# Quark_One.net
KiCad netlist of a schematic drawn in EAGLE
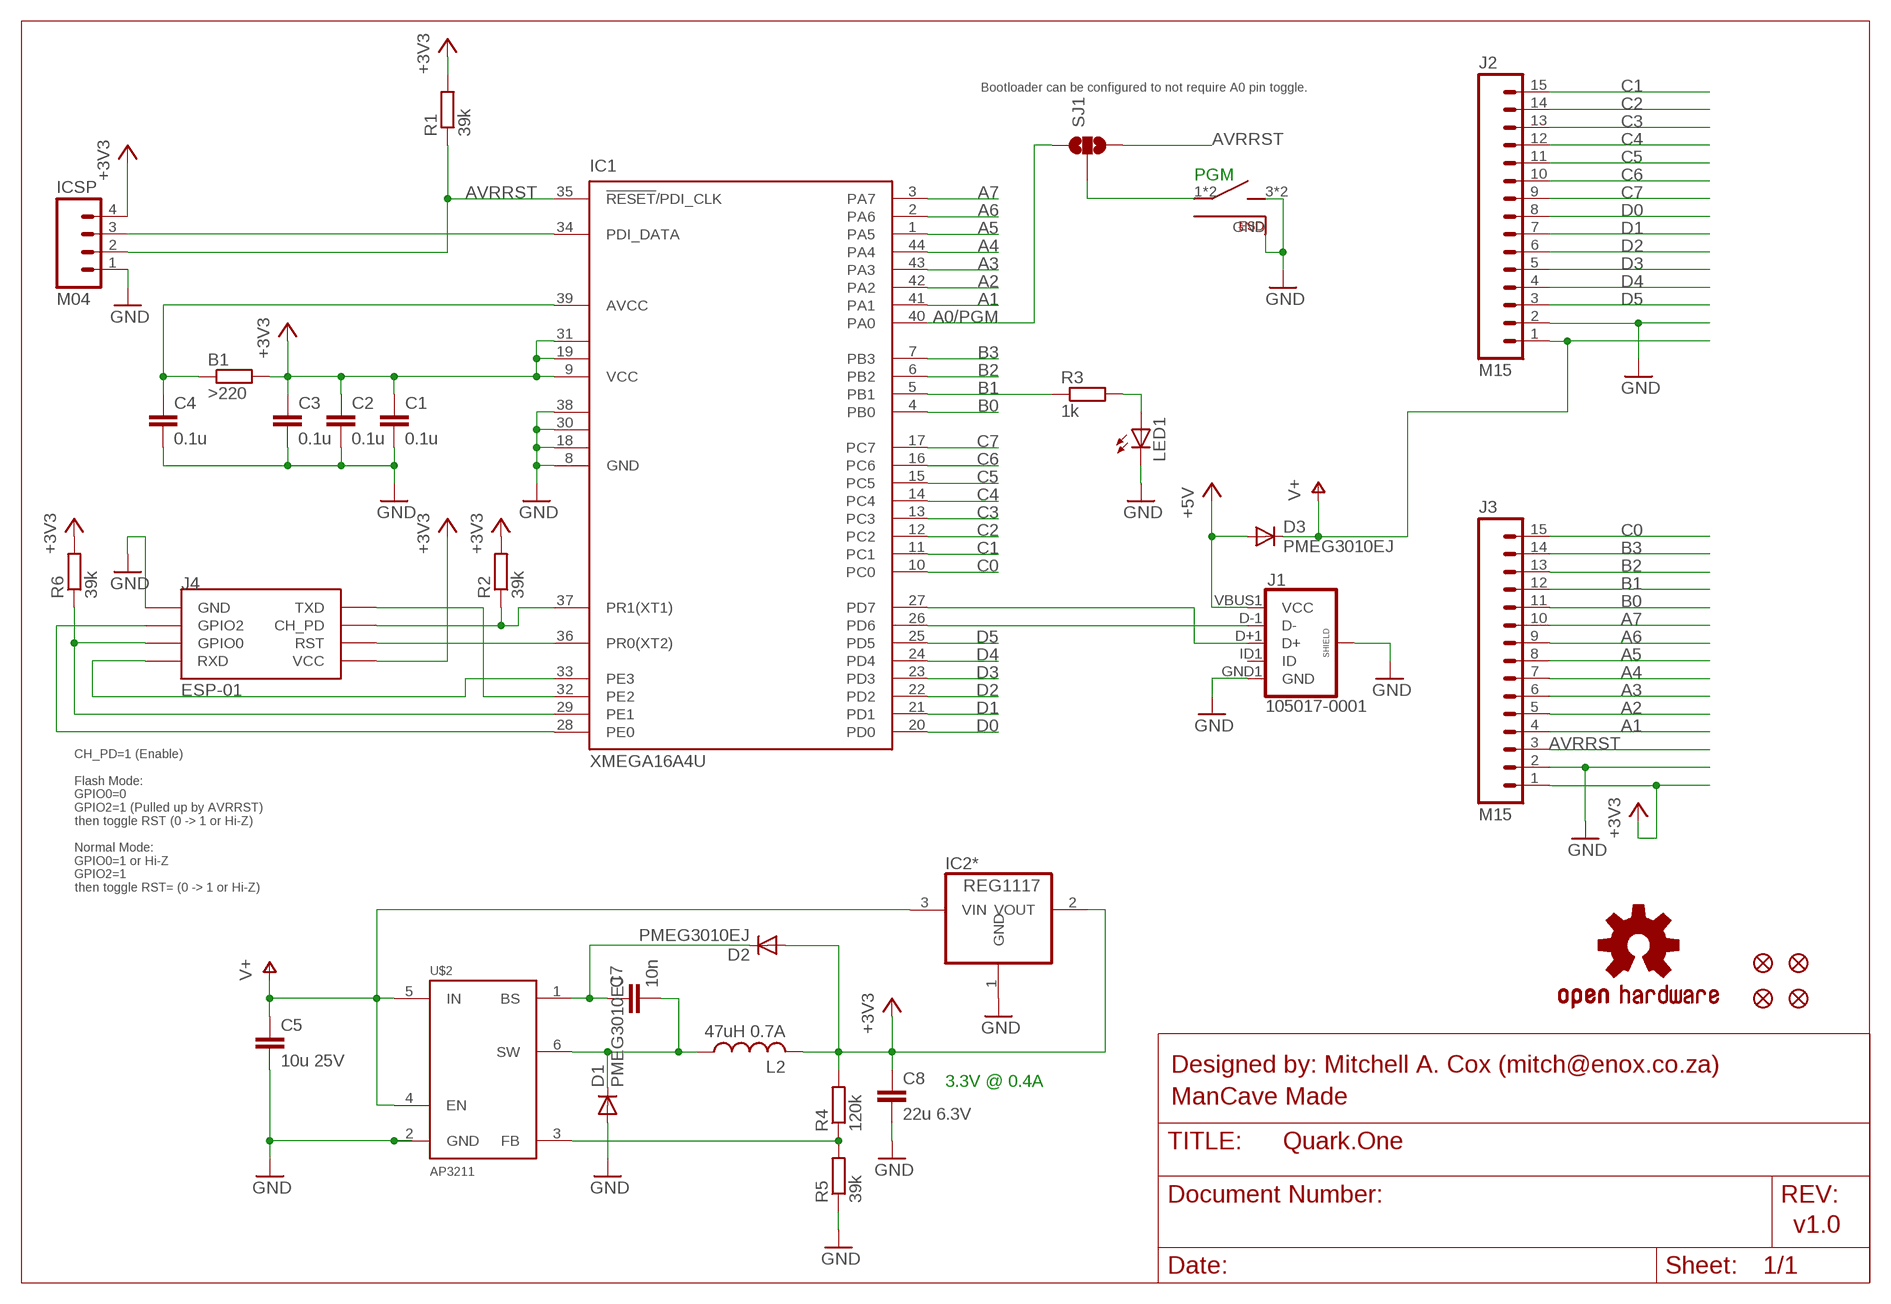
[diagram p0: schematic, sheet 1]

(export (version "E")
  (design (tool "Eeschema 10.0.6"))
  (components
    (comp (ref "B1")
      (value ">220")
      (footprint "eagle-import:R0603")
      (libsource (lib "eagle-import") (part "R-EU_R0603"))
    )
    (comp (ref "C1")
      (value "0.1u")
      (footprint "eagle-import:C0603")
      (libsource (lib "eagle-import") (part "C-EUC0603"))
    )
    (comp (ref "C2")
      (value "0.1u")
      (footprint "eagle-import:C0603")
      (libsource (lib "eagle-import") (part "C-EUC0603"))
    )
    (comp (ref "C3")
      (value "0.1u")
      (footprint "eagle-import:C0603")
      (libsource (lib "eagle-import") (part "C-EUC0603"))
    )
    (comp (ref "C4")
      (value "0.1u")
      (footprint "eagle-import:C0603")
      (libsource (lib "eagle-import") (part "C-EUC0603"))
    )
    (comp (ref "C5")
      (value "10u 25V")
      (footprint "eagle-import:C0805")
      (libsource (lib "eagle-import") (part "C-EUC0805"))
    )
    (comp (ref "C7")
      (value "10n")
      (footprint "eagle-import:C0603")
      (libsource (lib "eagle-import") (part "C-EUC0603"))
    )
    (comp (ref "C8")
      (value "22u 6.3V")
      (footprint "eagle-import:C0805")
      (libsource (lib "eagle-import") (part "C-EUC0805"))
    )
    (comp (ref "D1")
      (value "PMEG3010EJ")
      (footprint "eagle-import:SOD-323")
      (libsource (lib "eagle-import") (part "DIODESOD"))
    )
    (comp (ref "D2")
      (value "PMEG3010EJ")
      (footprint "eagle-import:SOD-323")
      (libsource (lib "eagle-import") (part "DIODESOD"))
    )
    (comp (ref "D3")
      (value "PMEG3010EJ")
      (footprint "eagle-import:SOD-323")
      (libsource (lib "eagle-import") (part "DIODESOD"))
    )
    (comp (ref "IC1")
      (value "XMEGA16A4U")
      (footprint "eagle-import:TQFP44")
      (libsource (lib "eagle-import") (part "XMEGA16A4A"))
    )
    (comp (ref "IC2*")
      (value "REG1117")
      (footprint "eagle-import:SOT223")
      (libsource (lib "eagle-import") (part "REG1117"))
    )
    (comp (ref "ICSP")
      (value "M04")
      (footprint "eagle-import:1X04-LOCK")
      (libsource (lib "eagle-import") (part "M04"))
    )
    (comp (ref "J1")
      (value "105017-0001")
      (footprint "eagle-import:USB-MICROB")
      (libsource (lib "eagle-import") (part "USB-MICRO"))
    )
    (comp (ref "J2")
      (value "M15")
      (footprint "eagle-import:1X15")
      (libsource (lib "eagle-import") (part "M15"))
    )
    (comp (ref "J3")
      (value "M15")
      (footprint "eagle-import:1X15")
      (libsource (lib "eagle-import") (part "M15"))
    )
    (comp (ref "J4")
      (value "ESP-01")
      (footprint "eagle-import:ESP01")
      (libsource (lib "eagle-import") (part "ESP01"))
    )
    (comp (ref "JP1")
      (value "FIDUCIALUFIDUCIAL")
      (footprint "eagle-import:MICRO-FIDUCIAL")
      (libsource (lib "eagle-import") (part "FIDUCIALUFIDUCIAL"))
    )
    (comp (ref "JP2")
      (value "FIDUCIALUFIDUCIAL")
      (footprint "eagle-import:MICRO-FIDUCIAL")
      (libsource (lib "eagle-import") (part "FIDUCIALUFIDUCIAL"))
    )
    (comp (ref "JP3")
      (value "FIDUCIALUFIDUCIAL")
      (footprint "eagle-import:MICRO-FIDUCIAL")
      (libsource (lib "eagle-import") (part "FIDUCIALUFIDUCIAL"))
    )
    (comp (ref "JP4")
      (value "FIDUCIALUFIDUCIAL")
      (footprint "eagle-import:MICRO-FIDUCIAL")
      (libsource (lib "eagle-import") (part "FIDUCIALUFIDUCIAL"))
    )
    (comp (ref "L2")
      (value "47uH 0.7A")
      (footprint "eagle-import:LQH44P")
      (libsource (lib "eagle-import") (part "L"))
    )
    (comp (ref "LED1")
      (value "LEDCHIPLED_0603")
      (footprint "eagle-import:CHIPLED_0603")
      (libsource (lib "eagle-import") (part "LEDCHIPLED_0603"))
    )
    (comp (ref "R1")
      (value "39k")
      (footprint "eagle-import:R0603")
      (libsource (lib "eagle-import") (part "R-EU_R0603"))
    )
    (comp (ref "R2")
      (value "39k")
      (footprint "eagle-import:R0603")
      (libsource (lib "eagle-import") (part "R-EU_R0603"))
    )
    (comp (ref "R3")
      (value "1k")
      (footprint "eagle-import:R0603")
      (libsource (lib "eagle-import") (part "R-EU_R0603"))
    )
    (comp (ref "R4")
      (value "120k")
      (footprint "eagle-import:R0603")
      (libsource (lib "eagle-import") (part "R-EU_R0603"))
    )
    (comp (ref "R5")
      (value "39k")
      (footprint "eagle-import:R0603")
      (libsource (lib "eagle-import") (part "R-EU_R0603"))
    )
    (comp (ref "R6")
      (value "39k")
      (footprint "eagle-import:R0603")
      (libsource (lib "eagle-import") (part "R-EU_R0603"))
    )
    (comp (ref "S1")
      (value "PTS840")
      (footprint "eagle-import:PTS840-SW")
      (libsource (lib "eagle-import") (part "PTS840"))
    )
    (comp (ref "SJ1")
      (value "SOLDERJUMPER_2WAY-OLDPASTE2&3")
      (footprint "eagle-import:SJ_3_PASTE2&3")
      (libsource (lib "eagle-import") (part "SOLDERJUMPER_2WAY-OLDPASTE2&3"))
    )
    (comp (ref "U$1")
      (value "OSHW")
      (footprint "eagle-import:OSHW-S")
      (libsource (lib "eagle-import") (part "OSHW"))
    )
    (comp (ref "U$2")
      (value "AP3211")
      (footprint "eagle-import:SOT23-6")
      (libsource (lib "eagle-import") (part "AP3211"))
    )
  )
  (nets
    (net (code "1") (name "+3V3") (class "Default")
      (node (ref "B1") (pin "2") (pinfunction "2_2") (pintype "passive"))
      (node (ref "C1") (pin "1") (pinfunction "1_1") (pintype "passive"))
      (node (ref "C2") (pin "1") (pinfunction "1_1") (pintype "passive"))
      (node (ref "C3") (pin "1") (pinfunction "1_1") (pintype "passive"))
      (node (ref "C8") (pin "1") (pinfunction "1_1") (pintype "passive"))
      (node (ref "D2") (pin "2") (pinfunction "A_2") (pintype "passive"))
      (node (ref "IC1") (pin "19") (pinfunction "VCC1_19") (pintype "power_in"))
      (node (ref "IC1") (pin "31") (pinfunction "VCC2_31") (pintype "power_in"))
      (node (ref "IC1") (pin "9") (pinfunction "VCC_9") (pintype "power_in"))
      (node (ref "IC2*") (pin "2") (pinfunction "VOUT_2") (pintype "output"))
      (node (ref "ICSP") (pin "4") (pinfunction "4_4") (pintype "passive"))
      (node (ref "J3") (pin "1") (pinfunction "1_1") (pintype "passive"))
      (node (ref "J4") (pin "VCC") (pinfunction "VCC_VCC") (pintype "bidirectional"))
      (node (ref "L2") (pin "2") (pinfunction "2_2") (pintype "passive"))
      (node (ref "R1") (pin "2") (pinfunction "2_2") (pintype "passive"))
      (node (ref "R2") (pin "2") (pinfunction "2_2") (pintype "passive"))
      (node (ref "R4") (pin "2") (pinfunction "2_2") (pintype "passive"))
      (node (ref "R6") (pin "2") (pinfunction "2_2") (pintype "passive"))
    )
    (net (code "2") (name "+5V") (class "Default")
      (node (ref "D3") (pin "2") (pinfunction "A_2") (pintype "passive"))
      (node (ref "J1") (pin "VBUS1") (pinfunction "VCC_VBUS1") (pintype "bidirectional"))
    )
    (net (code "3") (name "/A0{slash}PGM") (class "Default")
      (node (ref "IC1") (pin "40") (pinfunction "PA0_40") (pintype "bidirectional"))
      (node (ref "SJ1") (pin "1") (pinfunction "1_1") (pintype "passive"))
    )
    (net (code "4") (name "/A1") (class "Default")
      (node (ref "IC1") (pin "41") (pinfunction "PA1_41") (pintype "bidirectional"))
      (node (ref "J3") (pin "4") (pinfunction "4_4") (pintype "passive"))
    )
    (net (code "5") (name "/A2") (class "Default")
      (node (ref "IC1") (pin "42") (pinfunction "PA2_42") (pintype "bidirectional"))
      (node (ref "J3") (pin "5") (pinfunction "5_5") (pintype "passive"))
    )
    (net (code "6") (name "/A3") (class "Default")
      (node (ref "IC1") (pin "43") (pinfunction "PA3_43") (pintype "bidirectional"))
      (node (ref "J3") (pin "6") (pinfunction "6_6") (pintype "passive"))
    )
    (net (code "7") (name "/A4") (class "Default")
      (node (ref "IC1") (pin "44") (pinfunction "PA4_44") (pintype "bidirectional"))
      (node (ref "J3") (pin "7") (pinfunction "7_7") (pintype "passive"))
    )
    (net (code "8") (name "/A5") (class "Default")
      (node (ref "IC1") (pin "1") (pinfunction "PA5_1") (pintype "bidirectional"))
      (node (ref "J3") (pin "8") (pinfunction "8_8") (pintype "passive"))
    )
    (net (code "9") (name "/A6") (class "Default")
      (node (ref "IC1") (pin "2") (pinfunction "PA6_2") (pintype "bidirectional"))
      (node (ref "J3") (pin "9") (pinfunction "9_9") (pintype "passive"))
    )
    (net (code "10") (name "/A7") (class "Default")
      (node (ref "IC1") (pin "3") (pinfunction "PA7_3") (pintype "bidirectional"))
      (node (ref "J3") (pin "10") (pinfunction "10_10") (pintype "passive"))
    )
    (net (code "11") (name "/AVRRST") (class "Default")
      (node (ref "IC1") (pin "35") (pinfunction "~{RESET}/PDI_CLK_35") (pintype "bidirectional"))
      (node (ref "ICSP") (pin "2") (pinfunction "2_2") (pintype "passive"))
      (node (ref "J3") (pin "3") (pinfunction "3_3") (pintype "passive"))
      (node (ref "R1") (pin "1") (pinfunction "1_1") (pintype "passive"))
      (node (ref "SJ1") (pin "3") (pinfunction "3_3") (pintype "passive"))
    )
    (net (code "12") (name "/B0") (class "Default")
      (node (ref "IC1") (pin "4") (pinfunction "PB0_4") (pintype "bidirectional"))
      (node (ref "J3") (pin "11") (pinfunction "11_11") (pintype "passive"))
    )
    (net (code "13") (name "/B1") (class "Default")
      (node (ref "IC1") (pin "5") (pinfunction "PB1_5") (pintype "bidirectional"))
      (node (ref "J3") (pin "12") (pinfunction "12_12") (pintype "passive"))
      (node (ref "R3") (pin "1") (pinfunction "1_1") (pintype "passive"))
    )
    (net (code "14") (name "/B2") (class "Default")
      (node (ref "IC1") (pin "6") (pinfunction "PB2_6") (pintype "bidirectional"))
      (node (ref "J3") (pin "13") (pinfunction "13_13") (pintype "passive"))
    )
    (net (code "15") (name "/B3") (class "Default")
      (node (ref "IC1") (pin "7") (pinfunction "PB3_7") (pintype "bidirectional"))
      (node (ref "J3") (pin "14") (pinfunction "14_14") (pintype "passive"))
    )
    (net (code "16") (name "/C0") (class "Default")
      (node (ref "IC1") (pin "10") (pinfunction "PC0_10") (pintype "bidirectional"))
      (node (ref "J3") (pin "15") (pinfunction "15_15") (pintype "passive"))
    )
    (net (code "17") (name "/C1") (class "Default")
      (node (ref "IC1") (pin "11") (pinfunction "PC1_11") (pintype "bidirectional"))
      (node (ref "J2") (pin "15") (pinfunction "15_15") (pintype "passive"))
    )
    (net (code "18") (name "/C2") (class "Default")
      (node (ref "IC1") (pin "12") (pinfunction "PC2_12") (pintype "bidirectional"))
      (node (ref "J2") (pin "14") (pinfunction "14_14") (pintype "passive"))
    )
    (net (code "19") (name "/C3") (class "Default")
      (node (ref "IC1") (pin "13") (pinfunction "PC3_13") (pintype "bidirectional"))
      (node (ref "J2") (pin "13") (pinfunction "13_13") (pintype "passive"))
    )
    (net (code "20") (name "/C4") (class "Default")
      (node (ref "IC1") (pin "14") (pinfunction "PC4_14") (pintype "bidirectional"))
      (node (ref "J2") (pin "12") (pinfunction "12_12") (pintype "passive"))
    )
    (net (code "21") (name "/C5") (class "Default")
      (node (ref "IC1") (pin "15") (pinfunction "PC5_15") (pintype "bidirectional"))
      (node (ref "J2") (pin "11") (pinfunction "11_11") (pintype "passive"))
    )
    (net (code "22") (name "/C6") (class "Default")
      (node (ref "IC1") (pin "16") (pinfunction "PC6_16") (pintype "bidirectional"))
      (node (ref "J2") (pin "10") (pinfunction "10_10") (pintype "passive"))
    )
    (net (code "23") (name "/C7") (class "Default")
      (node (ref "IC1") (pin "17") (pinfunction "PC7_17") (pintype "bidirectional"))
      (node (ref "J2") (pin "9") (pinfunction "9_9") (pintype "passive"))
    )
    (net (code "24") (name "/D0") (class "Default")
      (node (ref "IC1") (pin "20") (pinfunction "PD0_20") (pintype "bidirectional"))
      (node (ref "J2") (pin "8") (pinfunction "8_8") (pintype "passive"))
    )
    (net (code "25") (name "/D1") (class "Default")
      (node (ref "IC1") (pin "21") (pinfunction "PD1_21") (pintype "bidirectional"))
      (node (ref "J2") (pin "7") (pinfunction "7_7") (pintype "passive"))
    )
    (net (code "26") (name "/D2") (class "Default")
      (node (ref "IC1") (pin "22") (pinfunction "PD2_22") (pintype "bidirectional"))
      (node (ref "J2") (pin "6") (pinfunction "6_6") (pintype "passive"))
    )
    (net (code "27") (name "/D3") (class "Default")
      (node (ref "IC1") (pin "23") (pinfunction "PD3_23") (pintype "bidirectional"))
      (node (ref "J2") (pin "5") (pinfunction "5_5") (pintype "passive"))
    )
    (net (code "28") (name "/D4") (class "Default")
      (node (ref "IC1") (pin "24") (pinfunction "PD4_24") (pintype "bidirectional"))
      (node (ref "J2") (pin "4") (pinfunction "4_4") (pintype "passive"))
    )
    (net (code "29") (name "/D5") (class "Default")
      (node (ref "IC1") (pin "25") (pinfunction "PD5_25") (pintype "bidirectional"))
      (node (ref "J2") (pin "3") (pinfunction "3_3") (pintype "passive"))
    )
    (net (code "30") (name "GND") (class "Default")
      (node (ref "C1") (pin "2") (pinfunction "2_2") (pintype "passive"))
      (node (ref "C2") (pin "2") (pinfunction "2_2") (pintype "passive"))
      (node (ref "C3") (pin "2") (pinfunction "2_2") (pintype "passive"))
      (node (ref "C4") (pin "2") (pinfunction "2_2") (pintype "passive"))
      (node (ref "C5") (pin "2") (pinfunction "2_2") (pintype "passive"))
      (node (ref "C8") (pin "2") (pinfunction "2_2") (pintype "passive"))
      (node (ref "D1") (pin "2") (pinfunction "A_2") (pintype "passive"))
      (node (ref "IC1") (pin "18") (pinfunction "GND1_18") (pintype "power_in"))
      (node (ref "IC1") (pin "30") (pinfunction "GND2_30") (pintype "power_in"))
      (node (ref "IC1") (pin "38") (pinfunction "GND3_38") (pintype "power_in"))
      (node (ref "IC1") (pin "8") (pinfunction "GND_8") (pintype "power_in"))
      (node (ref "IC2*") (pin "1") (pinfunction "GND_1") (pintype "power_in"))
      (node (ref "ICSP") (pin "1") (pinfunction "1_1") (pintype "passive"))
      (node (ref "J1") (pin "GND1") (pinfunction "GND_GND1") (pintype "bidirectional"))
      (node (ref "J1") (pin "P$1") (pinfunction "SHIELD_P$1") (pintype "bidirectional"))
      (node (ref "J1") (pin "P$2") (pinfunction "SHIELD_P$2") (pintype "bidirectional"))
      (node (ref "J1") (pin "P$7") (pinfunction "SHIELD_P$7") (pintype "bidirectional"))
      (node (ref "J1") (pin "P$8") (pinfunction "SHIELD_P$8") (pintype "bidirectional"))
      (node (ref "J1") (pin "SHIELD") (pinfunction "SHIELD_SHIELD") (pintype "bidirectional"))
      (node (ref "J1") (pin "SHIELD2") (pinfunction "SHIELD_SHIELD2") (pintype "bidirectional"))
      (node (ref "J2") (pin "2") (pinfunction "2_2") (pintype "passive"))
      (node (ref "J3") (pin "2") (pinfunction "2_2") (pintype "passive"))
      (node (ref "J4") (pin "GND") (pinfunction "GND_GND") (pintype "bidirectional"))
      (node (ref "LED1") (pin "C") (pinfunction "C_C") (pintype "passive"))
      (node (ref "R5") (pin "1") (pinfunction "1_1") (pintype "passive"))
      (node (ref "S1") (pin "3") (pinfunction "P$1_3") (pintype "bidirectional"))
      (node (ref "S1") (pin "4") (pinfunction "P$1_4") (pintype "bidirectional"))
      (node (ref "S1") (pin "GND") (pinfunction "P$2_GND") (pintype "power_in"))
      (node (ref "U$2") (pin "2") (pinfunction "GND_2") (pintype "power_in"))
    )
    (net (code "31") (name "Net-(D1-C)") (class "Default")
      (node (ref "C7") (pin "2") (pinfunction "2_2") (pintype "passive"))
      (node (ref "D1") (pin "1") (pinfunction "C_1") (pintype "passive"))
      (node (ref "L2") (pin "1") (pinfunction "1_1") (pintype "passive"))
      (node (ref "U$2") (pin "6") (pinfunction "SW_6") (pintype "bidirectional"))
    )
    (net (code "32") (name "Net-(D2-C)") (class "Default")
      (node (ref "C7") (pin "1") (pinfunction "1_1") (pintype "passive"))
      (node (ref "D2") (pin "1") (pinfunction "C_1") (pintype "passive"))
      (node (ref "U$2") (pin "1") (pinfunction "BS_1") (pintype "bidirectional"))
    )
    (net (code "33") (name "Net-(IC1-AVCC)") (class "Default")
      (node (ref "B1") (pin "1") (pinfunction "1_1") (pintype "passive"))
      (node (ref "C4") (pin "1") (pinfunction "1_1") (pintype "passive"))
      (node (ref "IC1") (pin "39") (pinfunction "AVCC_39") (pintype "power_in"))
    )
    (net (code "34") (name "Net-(IC1-PD6)") (class "Default")
      (node (ref "IC1") (pin "26") (pinfunction "PD6_26") (pintype "bidirectional"))
      (node (ref "J1") (pin "D-1") (pinfunction "D-_D-1") (pintype "bidirectional"))
    )
    (net (code "35") (name "Net-(IC1-PD7)") (class "Default")
      (node (ref "IC1") (pin "27") (pinfunction "PD7_27") (pintype "bidirectional"))
      (node (ref "J1") (pin "D+1") (pinfunction "D+_D+1") (pintype "bidirectional"))
    )
    (net (code "36") (name "Net-(IC1-PDI_DATA)") (class "Default")
      (node (ref "IC1") (pin "34") (pinfunction "PDI_DATA_34") (pintype "bidirectional"))
      (node (ref "ICSP") (pin "3") (pinfunction "3_3") (pintype "passive"))
    )
    (net (code "37") (name "Net-(IC1-PE0)") (class "Default")
      (node (ref "IC1") (pin "28") (pinfunction "PE0_28") (pintype "bidirectional"))
      (node (ref "J4") (pin "GPIO2") (pinfunction "GPIO2_GPIO2") (pintype "bidirectional"))
    )
    (net (code "38") (name "Net-(IC1-PE1)") (class "Default")
      (node (ref "IC1") (pin "29") (pinfunction "PE1_29") (pintype "bidirectional"))
      (node (ref "J4") (pin "GPIO0") (pinfunction "GPIO0_GPIO0") (pintype "bidirectional"))
      (node (ref "R6") (pin "1") (pinfunction "1_1") (pintype "passive"))
    )
    (net (code "39") (name "Net-(IC1-PE2)") (class "Default")
      (node (ref "IC1") (pin "32") (pinfunction "PE2_32") (pintype "bidirectional"))
      (node (ref "J4") (pin "TX") (pinfunction "TXD_TX") (pintype "bidirectional"))
    )
    (net (code "40") (name "Net-(IC1-PE3)") (class "Default")
      (node (ref "IC1") (pin "33") (pinfunction "PE3_33") (pintype "bidirectional"))
      (node (ref "J4") (pin "RX") (pinfunction "RXD_RX") (pintype "bidirectional"))
    )
    (net (code "41") (name "Net-(IC1-PR0(XT2))") (class "Default")
      (node (ref "IC1") (pin "36") (pinfunction "PR0(XT2)_36") (pintype "bidirectional"))
      (node (ref "J4") (pin "RST") (pinfunction "RST_RST") (pintype "bidirectional"))
    )
    (net (code "42") (name "Net-(IC1-PR1(XT1))") (class "Default")
      (node (ref "IC1") (pin "37") (pinfunction "PR1(XT1)_37") (pintype "bidirectional"))
      (node (ref "J4") (pin "CH_PD") (pinfunction "CH_PD_CH_PD") (pintype "bidirectional"))
      (node (ref "R2") (pin "1") (pinfunction "1_1") (pintype "passive"))
    )
    (net (code "43") (name "Net-(LED1-PadA)") (class "Default")
      (node (ref "LED1") (pin "A") (pinfunction "A_A") (pintype "passive"))
      (node (ref "R3") (pin "2") (pinfunction "2_2") (pintype "passive"))
    )
    (net (code "44") (name "Net-(S1-P$0-Pad1)") (class "Default")
      (node (ref "S1") (pin "1") (pinfunction "P$0_1") (pintype "bidirectional"))
      (node (ref "S1") (pin "2") (pinfunction "P$0_2") (pintype "bidirectional"))
      (node (ref "SJ1") (pin "2") (pinfunction "2_2") (pintype "passive"))
    )
    (net (code "45") (name "Net-(U$2-FB)") (class "Default")
      (node (ref "R4") (pin "1") (pinfunction "1_1") (pintype "passive"))
      (node (ref "R5") (pin "2") (pinfunction "2_2") (pintype "passive"))
      (node (ref "U$2") (pin "3") (pinfunction "FB_3") (pintype "bidirectional"))
    )
    (net (code "46") (name "V+") (class "Default")
      (node (ref "C5") (pin "1") (pinfunction "1_1") (pintype "passive"))
      (node (ref "D3") (pin "1") (pinfunction "C_1") (pintype "passive"))
      (node (ref "IC2*") (pin "3") (pinfunction "VIN_3") (pintype "input"))
      (node (ref "J2") (pin "1") (pinfunction "1_1") (pintype "passive"))
      (node (ref "U$2") (pin "4") (pinfunction "EN_4") (pintype "bidirectional"))
      (node (ref "U$2") (pin "5") (pinfunction "IN_5") (pintype "bidirectional"))
    )
    (net (code "47") (name "unconnected-(J1-ID-PadID1)") (class "Default")
      (node (ref "J1") (pin "ID1") (pinfunction "ID_ID1") (pintype "bidirectional"))
    )
  )
)
